# mainboard_rs485_v1_1.net
KiCad netlist of a schematic drawn in Altium Designer
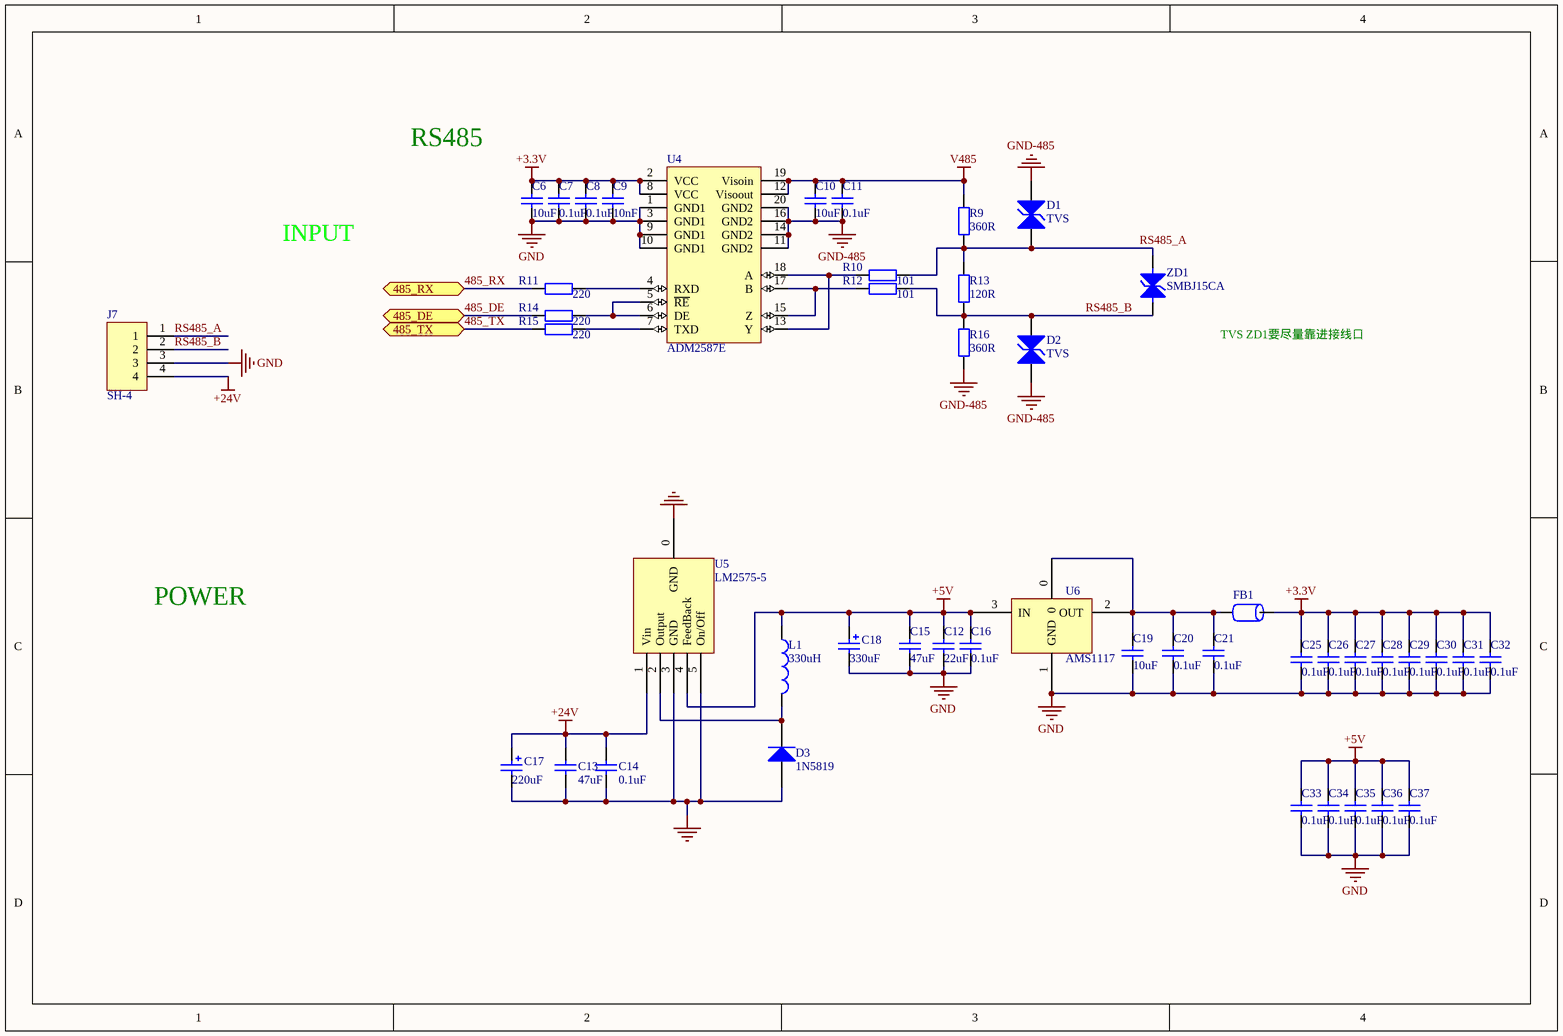
[diagram p0: mainboard_rs485.v1.1.SchDoc]

(export (version "E")
  (design (tool "Eeschema 10.0.6"))
  (components
    (comp (ref "C6")
      (value "10uF")
      (footprint "0805")
      (description "Capacitor")
      (fields (field (name "PUBLISHER") "Altium Limited"))
      (libsource (lib "TIAN's Schlib") (part "Cap"))
    )
    (comp (ref "C7")
      (value "0.1uF")
      (footprint "0805")
      (description "Capacitor")
      (fields (field (name "PUBLISHER") "Altium Limited"))
      (libsource (lib "TIAN's Schlib") (part "Cap"))
    )
    (comp (ref "C8")
      (value "0.1uF")
      (footprint "0805")
      (description "Capacitor")
      (fields (field (name "PUBLISHER") "Altium Limited"))
      (libsource (lib "TIAN's Schlib") (part "Cap"))
    )
    (comp (ref "C9")
      (value "10nF")
      (footprint "0805")
      (description "Capacitor")
      (fields (field (name "PUBLISHER") "Altium Limited"))
      (libsource (lib "TIAN's Schlib") (part "Cap"))
    )
    (comp (ref "C10")
      (value "10uF")
      (footprint "0805")
      (description "Capacitor")
      (fields (field (name "PUBLISHER") "Altium Limited"))
      (libsource (lib "TIAN's Schlib") (part "Cap"))
    )
    (comp (ref "C11")
      (value "0.1uF")
      (footprint "0805")
      (description "Capacitor")
      (fields (field (name "PUBLISHER") "Altium Limited"))
      (libsource (lib "TIAN's Schlib") (part "Cap"))
    )
    (comp (ref "C12") (value "22uF") (footprint "1206") (libsource (lib "Componet") (part "Cap0805")))
    (comp (ref "C13")
      (value "47uF")
      (footprint "1812")
      (description "Capacitor")
      (fields (field (name "PUBLISHER") "Altium Limited"))
      (libsource (lib "Miscellaneous Devices") (part "Cap"))
    )
    (comp (ref "C14")
      (value "0.1uF")
      (footprint "0805")
      (description "Capacitor")
      (fields (field (name "PUBLISHER") "Altium Limited"))
      (libsource (lib "Miscellaneous Devices") (part "Cap"))
    )
    (comp (ref "C15") (value "47uF") (footprint "1812") (libsource (lib "Componet") (part "Cap0805")))
    (comp (ref "C16") (value "0.1uF") (footprint "0805") (libsource (lib "Componet") (part "Cap0805")))
    (comp (ref "C17")
      (value "220uF")
      (footprint "CAP-5mm")
      (description "Polarized Capacitor (Radial)")
      (fields (field (name "PUBLISHER") "Altium Limited"))
      (libsource (lib "Miscellaneous Devices") (part "Cap Pol1"))
    )
    (comp (ref "C18")
      (value "330uF")
      (footprint "CAP-5mm")
      (description "Polarized Capacitor (Radial)")
      (fields (field (name "PUBLISHER") "Altium Limited"))
      (libsource (lib "Miscellaneous Devices") (part "Cap Pol1"))
    )
    (comp (ref "C19") (value "10uF") (footprint "0805") (libsource (lib "Componet") (part "Cap0805")))
    (comp (ref "C20") (value "0.1uF") (footprint "0805") (libsource (lib "Componet") (part "Cap0805")))
    (comp (ref "C21") (value "0.1uF") (footprint "0805") (libsource (lib "Componet") (part "Cap0805")))
    (comp (ref "C25") (value "0.1uF") (footprint "0805") (libsource (lib "Componet") (part "Cap0805")))
    (comp (ref "C26") (value "0.1uF") (footprint "0805") (libsource (lib "Componet") (part "Cap0805")))
    (comp (ref "C27") (value "0.1uF") (footprint "0805") (libsource (lib "Componet") (part "Cap0805")))
    (comp (ref "C28") (value "0.1uF") (footprint "0805") (libsource (lib "Componet") (part "Cap0805")))
    (comp (ref "C29") (value "0.1uF") (footprint "0805") (libsource (lib "Componet") (part "Cap0805")))
    (comp (ref "C30") (value "0.1uF") (footprint "0805") (libsource (lib "Componet") (part "Cap0805")))
    (comp (ref "C31") (value "0.1uF") (footprint "0805") (libsource (lib "Componet") (part "Cap0805")))
    (comp (ref "C32") (value "0.1uF") (footprint "0805") (libsource (lib "Componet") (part "Cap0805")))
    (comp (ref "C33") (value "0.1uF") (footprint "0805") (libsource (lib "Componet") (part "Cap0805")))
    (comp (ref "C34") (value "0.1uF") (footprint "0805") (libsource (lib "Componet") (part "Cap0805")))
    (comp (ref "C35") (value "0.1uF") (footprint "0805") (libsource (lib "Componet") (part "Cap0805")))
    (comp (ref "C36") (value "0.1uF") (footprint "0805") (libsource (lib "Componet") (part "Cap0805")))
    (comp (ref "C37") (value "0.1uF") (footprint "0805") (libsource (lib "Componet") (part "Cap0805")))
    (comp (ref "D1")
      (value "TVS")
      (footprint "SMBJ_DO-214")
      (fields (field (name "PUBLISHER") "Altium Limited"))
      (libsource (lib "TIAN's Schlib") (part "TVS"))
    )
    (comp (ref "D2")
      (value "TVS")
      (footprint "SMBJ_DO-214")
      (fields (field (name "PUBLISHER") "Altium Limited"))
      (libsource (lib "TIAN's Schlib") (part "TVS"))
    )
    (comp (ref "D3")
      (value "1N5819")
      (footprint "Diode_TP2")
      (description "High Conductance Fast Diode")
      (fields (field (name "PUBLISHER") "Altium Limited"))
      (libsource (lib "Miscellaneous Devices") (part "Diode 1N4148"))
    )
    (comp (ref "FB1") (value "FERRITE") (footprint "0805") (libsource (lib "Connector") (part "FERRITE")))
    (comp (ref "J7") (value "SH-4") (footprint "J381-180") (libsource (lib "Connector") (part "SH-4")))
    (comp (ref "L1")
      (value "330uH")
      (footprint "Inductance")
      (description "Inductor")
      (fields (field (name "PUBLISHER") "Altium Limited"))
      (libsource (lib "Miscellaneous Devices") (part "Inductor"))
    )
    (comp (ref "R9")
      (value "360R")
      (footprint "0805")
      (description "Resistor")
      (fields (field (name "PUBLISHER") "Altium Limited"))
      (libsource (lib "TIAN's Schlib") (part "Res2"))
    )
    (comp (ref "R10")
      (value "101")
      (footprint "0805")
      (description "Resistor")
      (fields (field (name "PUBLISHER") "Altium Limited"))
      (libsource (lib "") (part "Res2_1"))
    )
    (comp (ref "R11")
      (value "220")
      (footprint "0805")
      (description "Resistor")
      (fields (field (name "PUBLISHER") "Altium Limited"))
      (libsource (lib "TIAN's Schlib") (part "Res2"))
    )
    (comp (ref "R12")
      (value "101")
      (footprint "0805")
      (description "Resistor")
      (fields (field (name "PUBLISHER") "Altium Limited"))
      (libsource (lib "") (part "Res2_1"))
    )
    (comp (ref "R13")
      (value "120R")
      (footprint "0805")
      (description "Resistor")
      (fields (field (name "PUBLISHER") "Altium Limited"))
      (libsource (lib "TIAN's Schlib") (part "Res2"))
    )
    (comp (ref "R14")
      (value "220")
      (footprint "0805")
      (description "Resistor")
      (fields (field (name "PUBLISHER") "Altium Limited"))
      (libsource (lib "TIAN's Schlib") (part "Res2"))
    )
    (comp (ref "R15")
      (value "220")
      (footprint "0805")
      (description "Resistor")
      (fields (field (name "PUBLISHER") "Altium Limited"))
      (libsource (lib "TIAN's Schlib") (part "Res2"))
    )
    (comp (ref "R16")
      (value "360R")
      (footprint "0805")
      (description "Resistor")
      (fields (field (name "PUBLISHER") "Altium Limited"))
      (libsource (lib "TIAN's Schlib") (part "Res2"))
    )
    (comp (ref "U4")
      (value "ADM2587E")
      (footprint "SOIC_W_20")
      (description "isolated DC-DC RS485")
      (libsource (lib "TIAN's Schlib") (part "ADM2587E"))
    )
    (comp (ref "U5") (value "LM2575-5") (footprint "TO-263") (libsource (lib "Leon") (part "LM25XX")))
    (comp (ref "U6") (value "AMS1117") (footprint "TO-223") (libsource (lib "Chip") (part "AMS1117")))
    (comp (ref "ZD1")
      (value "SMBJ15CA")
      (footprint "DO-214AA/SMB")
      (description "瞬态抑制二极管")
      (libsource (lib "ALARM") (part "TVS"))
    )
  )
  (nets
    (net (code "1") (name "+3.3V") (class "Default")
      (node (ref "C25") (pin "2") (pinfunction "2_2") (pintype "passive"))
      (node (ref "C26") (pin "2") (pinfunction "2_2") (pintype "passive"))
      (node (ref "C27") (pin "2") (pinfunction "2_2") (pintype "passive"))
      (node (ref "C28") (pin "2") (pinfunction "2_2") (pintype "passive"))
      (node (ref "C29") (pin "2") (pinfunction "2_2") (pintype "passive"))
      (node (ref "C30") (pin "2") (pinfunction "2_2") (pintype "passive"))
      (node (ref "C31") (pin "2") (pinfunction "2_2") (pintype "passive"))
      (node (ref "C32") (pin "2") (pinfunction "2_2") (pintype "passive"))
      (node (ref "C6") (pin "2") (pinfunction "2_2") (pintype "passive"))
      (node (ref "C7") (pin "2") (pinfunction "2_2") (pintype "passive"))
      (node (ref "C8") (pin "2") (pinfunction "2_2") (pintype "passive"))
      (node (ref "C9") (pin "2") (pinfunction "2_2") (pintype "passive"))
      (node (ref "FB1") (pin "2") (pinfunction "2_2") (pintype "passive"))
      (node (ref "U4") (pin "2") (pinfunction "VCC_2") (pintype "passive"))
      (node (ref "U4") (pin "8") (pinfunction "VCC_8") (pintype "passive"))
    )
    (net (code "2") (name "+5V") (class "Default")
      (node (ref "C12") (pin "2") (pinfunction "2_2") (pintype "passive"))
      (node (ref "C15") (pin "2") (pinfunction "2_2") (pintype "passive"))
      (node (ref "C16") (pin "2") (pinfunction "2_2") (pintype "passive"))
      (node (ref "C18") (pin "1") (pinfunction "1_1") (pintype "passive"))
      (node (ref "C33") (pin "2") (pinfunction "2_2") (pintype "passive"))
      (node (ref "C34") (pin "2") (pinfunction "2_2") (pintype "passive"))
      (node (ref "C35") (pin "2") (pinfunction "2_2") (pintype "passive"))
      (node (ref "C36") (pin "2") (pinfunction "2_2") (pintype "passive"))
      (node (ref "C37") (pin "2") (pinfunction "2_2") (pintype "passive"))
      (node (ref "L1") (pin "1") (pinfunction "1_1") (pintype "passive"))
      (node (ref "U5") (pin "4") (pinfunction "FeedBack_4") (pintype "passive"))
      (node (ref "U6") (pin "3") (pinfunction "IN_3") (pintype "passive"))
    )
    (net (code "3") (name "+24V") (class "Default")
      (node (ref "C13") (pin "2") (pinfunction "2_2") (pintype "passive"))
      (node (ref "C14") (pin "2") (pinfunction "2_2") (pintype "passive"))
      (node (ref "C17") (pin "1") (pinfunction "1_1") (pintype "passive"))
      (node (ref "J7") (pin "4") (pinfunction "4_4") (pintype "passive"))
      (node (ref "U5") (pin "1") (pinfunction "Vin_1") (pintype "passive"))
    )
    (net (code "4") (name "/485_DE") (class "Default")
      (node (ref "R14") (pin "1") (pinfunction "1_1") (pintype "passive"))
    )
    (net (code "5") (name "/485_RX") (class "Default")
      (node (ref "R11") (pin "1") (pinfunction "1_1") (pintype "passive"))
    )
    (net (code "6") (name "/485_TX") (class "Default")
      (node (ref "R15") (pin "1") (pinfunction "1_1") (pintype "passive"))
    )
    (net (code "7") (name "/RS485_A") (class "Default")
      (node (ref "D1") (pin "2") (pinfunction "K_2") (pintype "passive"))
      (node (ref "J7") (pin "1") (pinfunction "1_1") (pintype "passive"))
      (node (ref "R10") (pin "2") (pinfunction "2_2") (pintype "passive"))
      (node (ref "R13") (pin "2") (pinfunction "2_2") (pintype "passive"))
      (node (ref "R9") (pin "1") (pinfunction "1_1") (pintype "passive"))
      (node (ref "ZD1") (pin "1") (pinfunction "1_1") (pintype "passive"))
    )
    (net (code "8") (name "/RS485_B") (class "Default")
      (node (ref "D2") (pin "2") (pinfunction "K_2") (pintype "passive"))
      (node (ref "J7") (pin "2") (pinfunction "2_2") (pintype "passive"))
      (node (ref "R12") (pin "2") (pinfunction "2_2") (pintype "passive"))
      (node (ref "R13") (pin "1") (pinfunction "1_1") (pintype "passive"))
      (node (ref "R16") (pin "2") (pinfunction "2_2") (pintype "passive"))
      (node (ref "ZD1") (pin "2") (pinfunction "2_2") (pintype "passive"))
    )
    (net (code "9") (name "GND") (class "Default")
      (node (ref "C12") (pin "1") (pinfunction "1_1") (pintype "passive"))
      (node (ref "C13") (pin "1") (pinfunction "1_1") (pintype "passive"))
      (node (ref "C14") (pin "1") (pinfunction "1_1") (pintype "passive"))
      (node (ref "C15") (pin "1") (pinfunction "1_1") (pintype "passive"))
      (node (ref "C16") (pin "1") (pinfunction "1_1") (pintype "passive"))
      (node (ref "C17") (pin "2") (pinfunction "2_2") (pintype "passive"))
      (node (ref "C18") (pin "2") (pinfunction "2_2") (pintype "passive"))
      (node (ref "C19") (pin "1") (pinfunction "1_1") (pintype "passive"))
      (node (ref "C20") (pin "1") (pinfunction "1_1") (pintype "passive"))
      (node (ref "C21") (pin "1") (pinfunction "1_1") (pintype "passive"))
      (node (ref "C25") (pin "1") (pinfunction "1_1") (pintype "passive"))
      (node (ref "C26") (pin "1") (pinfunction "1_1") (pintype "passive"))
      (node (ref "C27") (pin "1") (pinfunction "1_1") (pintype "passive"))
      (node (ref "C28") (pin "1") (pinfunction "1_1") (pintype "passive"))
      (node (ref "C29") (pin "1") (pinfunction "1_1") (pintype "passive"))
      (node (ref "C30") (pin "1") (pinfunction "1_1") (pintype "passive"))
      (node (ref "C31") (pin "1") (pinfunction "1_1") (pintype "passive"))
      (node (ref "C32") (pin "1") (pinfunction "1_1") (pintype "passive"))
      (node (ref "C33") (pin "1") (pinfunction "1_1") (pintype "passive"))
      (node (ref "C34") (pin "1") (pinfunction "1_1") (pintype "passive"))
      (node (ref "C35") (pin "1") (pinfunction "1_1") (pintype "passive"))
      (node (ref "C36") (pin "1") (pinfunction "1_1") (pintype "passive"))
      (node (ref "C37") (pin "1") (pinfunction "1_1") (pintype "passive"))
      (node (ref "C6") (pin "1") (pinfunction "1_1") (pintype "passive"))
      (node (ref "C7") (pin "1") (pinfunction "1_1") (pintype "passive"))
      (node (ref "C8") (pin "1") (pinfunction "1_1") (pintype "passive"))
      (node (ref "C9") (pin "1") (pinfunction "1_1") (pintype "passive"))
      (node (ref "D3") (pin "1") (pinfunction "A_1") (pintype "passive"))
      (node (ref "J7") (pin "3") (pinfunction "3_3") (pintype "passive"))
      (node (ref "U4") (pin "1") (pinfunction "GND1_1") (pintype "passive"))
      (node (ref "U4") (pin "10") (pinfunction "GND1_10") (pintype "passive"))
      (node (ref "U4") (pin "3") (pinfunction "GND1_3") (pintype "passive"))
      (node (ref "U4") (pin "9") (pinfunction "GND1_9") (pintype "passive"))
      (node (ref "U5") (pin "0") (pinfunction "GND_0") (pintype "passive"))
      (node (ref "U5") (pin "3") (pinfunction "GND_3") (pintype "passive"))
      (node (ref "U5") (pin "5") (pinfunction "On/Off_5") (pintype "passive"))
      (node (ref "U6") (pin "1") (pinfunction "GND_1") (pintype "passive"))
    )
    (net (code "10") (name "GND-485") (class "Default")
      (node (ref "C10") (pin "1") (pinfunction "1_1") (pintype "passive"))
      (node (ref "C11") (pin "1") (pinfunction "1_1") (pintype "passive"))
      (node (ref "D1") (pin "1") (pinfunction "A_1") (pintype "passive"))
      (node (ref "D2") (pin "1") (pinfunction "A_1") (pintype "passive"))
      (node (ref "R16") (pin "1") (pinfunction "1_1") (pintype "passive"))
      (node (ref "U4") (pin "11") (pinfunction "GND2_11") (pintype "passive"))
      (node (ref "U4") (pin "14") (pinfunction "GND2_14") (pintype "passive"))
      (node (ref "U4") (pin "16") (pinfunction "GND2_16") (pintype "passive"))
      (node (ref "U4") (pin "20") (pinfunction "GND2_20") (pintype "passive"))
    )
    (net (code "11") (name "Net-(D3-K)") (class "Default")
      (node (ref "D3") (pin "2") (pinfunction "K_2") (pintype "passive"))
      (node (ref "L1") (pin "2") (pinfunction "2_2") (pintype "passive"))
      (node (ref "U5") (pin "2") (pinfunction "Output_2") (pintype "passive"))
    )
    (net (code "12") (name "Net-(U4-A)") (class "Default")
      (node (ref "R10") (pin "1") (pinfunction "1_1") (pintype "passive"))
      (node (ref "U4") (pin "13") (pinfunction "Y_13") (pintype "bidirectional"))
      (node (ref "U4") (pin "18") (pinfunction "A_18") (pintype "bidirectional"))
    )
    (net (code "13") (name "Net-(U4-B)") (class "Default")
      (node (ref "R12") (pin "1") (pinfunction "1_1") (pintype "passive"))
      (node (ref "U4") (pin "15") (pinfunction "Z_15") (pintype "bidirectional"))
      (node (ref "U4") (pin "17") (pinfunction "B_17") (pintype "bidirectional"))
    )
    (net (code "14") (name "Net-(U4-DE)") (class "Default")
      (node (ref "R14") (pin "2") (pinfunction "2_2") (pintype "passive"))
      (node (ref "U4") (pin "5") (pinfunction "~{RE}_5") (pintype "bidirectional"))
      (node (ref "U4") (pin "6") (pinfunction "DE_6") (pintype "bidirectional"))
    )
    (net (code "15") (name "Net-(U4-RXD)") (class "Default")
      (node (ref "R11") (pin "2") (pinfunction "2_2") (pintype "passive"))
      (node (ref "U4") (pin "4") (pinfunction "RXD_4") (pintype "bidirectional"))
    )
    (net (code "16") (name "Net-(U4-TXD)") (class "Default")
      (node (ref "R15") (pin "2") (pinfunction "2_2") (pintype "passive"))
      (node (ref "U4") (pin "7") (pinfunction "TXD_7") (pintype "bidirectional"))
    )
    (net (code "17") (name "Net-(U6-OUT)") (class "Default")
      (node (ref "C19") (pin "2") (pinfunction "2_2") (pintype "passive"))
      (node (ref "C20") (pin "2") (pinfunction "2_2") (pintype "passive"))
      (node (ref "C21") (pin "2") (pinfunction "2_2") (pintype "passive"))
      (node (ref "FB1") (pin "1") (pinfunction "1_1") (pintype "passive"))
      (node (ref "U6") (pin "0") (pinfunction "0_0") (pintype "passive"))
      (node (ref "U6") (pin "2") (pinfunction "OUT_2") (pintype "passive"))
    )
    (net (code "18") (name "V485") (class "Default")
      (node (ref "C10") (pin "2") (pinfunction "2_2") (pintype "passive"))
      (node (ref "C11") (pin "2") (pinfunction "2_2") (pintype "passive"))
      (node (ref "R9") (pin "2") (pinfunction "2_2") (pintype "passive"))
      (node (ref "U4") (pin "12") (pinfunction "Visoout_12") (pintype "passive"))
      (node (ref "U4") (pin "19") (pinfunction "Visoin_19") (pintype "passive"))
    )
  )
)
